# dimmerPower3.net
KiCad netlist of a schematic drawn in EAGLE
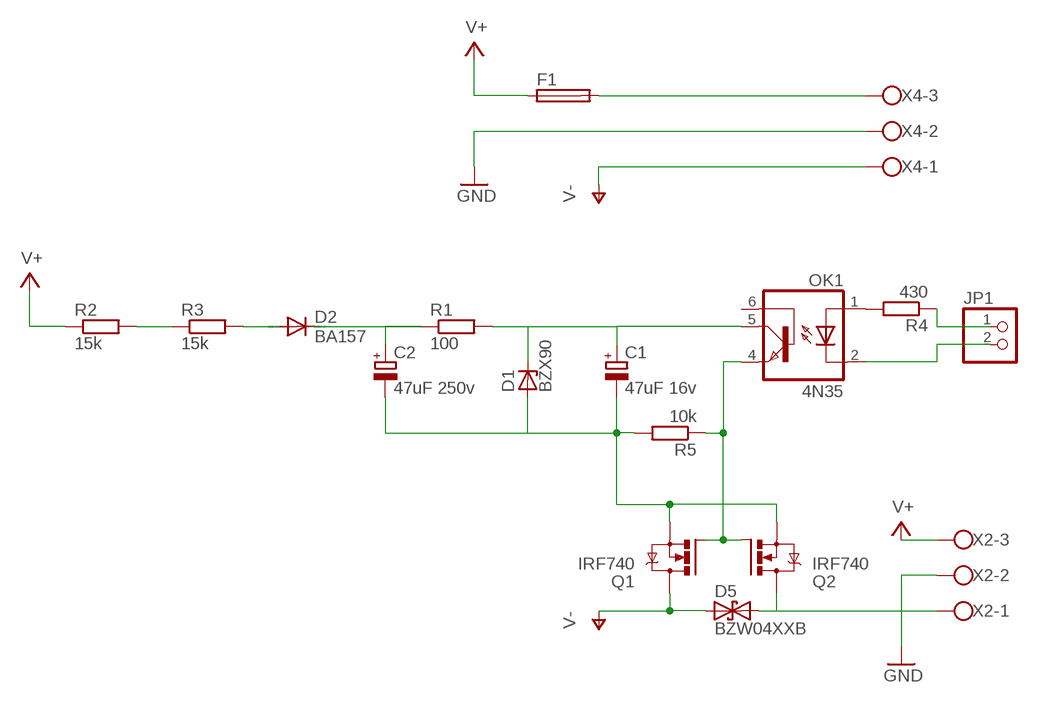
[diagram p0: schematic, sheet 1]

(export (version "E")
  (design (tool "Eeschema 10.0.6"))
  (components
    (comp (ref "C1")
      (value "47uF 16v")
      (footprint "eagle-import:E2,5-6")
      (libsource (lib "eagle-import") (part "CPOL-EUE2.5-6"))
    )
    (comp (ref "C2")
      (value "47uF 250v")
      (footprint "eagle-import:E5-13")
      (libsource (lib "eagle-import") (part "CPOL-EUE5-13"))
    )
    (comp (ref "D1")
      (value "BZX90")
      (footprint "eagle-import:DO34Z7")
      (libsource (lib "eagle-import") (part "BZX90"))
    )
    (comp (ref "D2")
      (value "BA157")
      (footprint "eagle-import:P1-10")
      (libsource (lib "eagle-import") (part "BA157"))
    )
    (comp (ref "D5")
      (value "BZW04XXB")
      (footprint "eagle-import:F126Z12")
      (libsource (lib "eagle-import") (part "BZW04XXB"))
    )
    (comp (ref "F1")
      (value "SH22,5")
      (footprint "eagle-import:SH22,5")
      (fields (field (name "MF") "SCHURTER") (field (name "MPN") "0031.8201"))
      (libsource (lib "eagle-import") (part "SH22,5"))
    )
    (comp (ref "JP1")
      (value "PINHD-1X2")
      (footprint "eagle-import:1X02")
      (libsource (lib "eagle-import") (part "PINHD-1X2"))
    )
    (comp (ref "OK1")
      (value "4N35")
      (footprint "eagle-import:DIL06")
      (fields (field (name "MF") "FAIRCHILD SEMICONDUCTOR"))
      (libsource (lib "eagle-import") (part "4N35"))
    )
    (comp (ref "Q1")
      (value "IRF740")
      (footprint "eagle-import:TO220BV")
      (libsource (lib "eagle-import") (part "IRF740"))
    )
    (comp (ref "Q2")
      (value "IRF740")
      (footprint "eagle-import:TO220BV")
      (libsource (lib "eagle-import") (part "IRF740"))
    )
    (comp (ref "R1")
      (value "100")
      (footprint "eagle-import:0204_7")
      (libsource (lib "eagle-import") (part "R-EU_0204/7"))
    )
    (comp (ref "R2")
      (value "15k")
      (footprint "eagle-import:P0613_15")
      (libsource (lib "eagle-import") (part "R-EU_0613/15"))
    )
    (comp (ref "R3")
      (value "15k")
      (footprint "eagle-import:P0613_15")
      (libsource (lib "eagle-import") (part "R-EU_0613/15"))
    )
    (comp (ref "R4")
      (value "430")
      (footprint "eagle-import:0204_7")
      (libsource (lib "eagle-import") (part "R-EU_0204/7"))
    )
    (comp (ref "R5")
      (value "10k")
      (footprint "eagle-import:0204_7")
      (libsource (lib "eagle-import") (part "R-EU_0204/7"))
    )
    (comp (ref "X2")
      (value "W237-103")
      (footprint "eagle-import:W237-103")
      (fields (field (name "MPN") "237-103"))
      (libsource (lib "eagle-import") (part "W237-103"))
    )
    (comp (ref "X4")
      (value "W237-103")
      (footprint "eagle-import:W237-103")
      (fields (field (name "MPN") "237-103"))
      (libsource (lib "eagle-import") (part "W237-103"))
    )
  )
  (nets
    (net (code "1") (name "GND") (class "Default")
      (node (ref "X2") (pin "2") (pinfunction "KL_2") (pintype "passive"))
      (node (ref "X4") (pin "2") (pinfunction "KL_2") (pintype "passive"))
    )
    (net (code "2") (name "Net-(C1-Pad-)") (class "Default")
      (node (ref "C1") (pin "-") (pinfunction "-_-") (pintype "passive"))
      (node (ref "C2") (pin "-") (pinfunction "-_-") (pintype "passive"))
      (node (ref "D1") (pin "A") (pinfunction "A_A") (pintype "passive"))
      (node (ref "Q1") (pin "S") (pinfunction "S_S") (pintype "passive"))
      (node (ref "Q2") (pin "S") (pinfunction "S_S") (pintype "passive"))
      (node (ref "R5") (pin "2") (pinfunction "2_2") (pintype "passive"))
    )
    (net (code "3") (name "Net-(C2-Pad+)") (class "Default")
      (node (ref "C2") (pin "+") (pinfunction "+_+") (pintype "passive"))
      (node (ref "D2") (pin "C") (pinfunction "C_C") (pintype "passive"))
      (node (ref "R1") (pin "1") (pinfunction "1_1") (pintype "passive"))
    )
    (net (code "4") (name "Net-(D2-PadA)") (class "Default")
      (node (ref "D2") (pin "A") (pinfunction "A_A") (pintype "passive"))
      (node (ref "R3") (pin "2") (pinfunction "2_2") (pintype "passive"))
    )
    (net (code "5") (name "Net-(D5-2)") (class "Default")
      (node (ref "D5") (pin "C") (pinfunction "2_C") (pintype "passive"))
      (node (ref "Q2") (pin "D") (pinfunction "D_D") (pintype "passive"))
      (node (ref "X2") (pin "1") (pinfunction "KL_1") (pintype "passive"))
    )
    (net (code "6") (name "Net-(JP1-Pad1)") (class "Default")
      (node (ref "JP1") (pin "1") (pinfunction "1_1") (pintype "passive"))
      (node (ref "R4") (pin "1") (pinfunction "1_1") (pintype "passive"))
    )
    (net (code "7") (name "Net-(OK1-A)") (class "Default")
      (node (ref "OK1") (pin "1") (pinfunction "A_1") (pintype "passive"))
      (node (ref "R4") (pin "2") (pinfunction "2_2") (pintype "passive"))
    )
    (net (code "8") (name "Net-(OK1-C)") (class "Default")
      (node (ref "JP1") (pin "2") (pinfunction "2_2") (pintype "passive"))
      (node (ref "OK1") (pin "2") (pinfunction "C_2") (pintype "passive"))
    )
    (net (code "9") (name "Net-(OK1-COL)") (class "Default")
      (node (ref "C1") (pin "+") (pinfunction "+_+") (pintype "passive"))
      (node (ref "D1") (pin "C") (pinfunction "C_C") (pintype "passive"))
      (node (ref "OK1") (pin "5") (pinfunction "COL_5") (pintype "passive"))
      (node (ref "R1") (pin "2") (pinfunction "2_2") (pintype "passive"))
    )
    (net (code "10") (name "Net-(OK1-EMI)") (class "Default")
      (node (ref "OK1") (pin "4") (pinfunction "EMI_4") (pintype "passive"))
      (node (ref "Q1") (pin "G") (pinfunction "G_G") (pintype "passive"))
      (node (ref "Q2") (pin "G") (pinfunction "G_G") (pintype "passive"))
      (node (ref "R5") (pin "1") (pinfunction "1_1") (pintype "passive"))
    )
    (net (code "11") (name "Net-(R2-Pad2)") (class "Default")
      (node (ref "R2") (pin "2") (pinfunction "2_2") (pintype "passive"))
      (node (ref "R3") (pin "1") (pinfunction "1_1") (pintype "passive"))
    )
    (net (code "12") (name "Net-(X4C-KL)") (class "Default")
      (node (ref "F1") (pin "2") (pinfunction "2_2") (pintype "passive"))
      (node (ref "X4") (pin "3") (pinfunction "KL_3") (pintype "passive"))
    )
    (net (code "13") (name "V+") (class "Default")
      (node (ref "F1") (pin "1") (pinfunction "1_1") (pintype "passive"))
      (node (ref "R2") (pin "1") (pinfunction "1_1") (pintype "passive"))
      (node (ref "X2") (pin "3") (pinfunction "KL_3") (pintype "passive"))
    )
    (net (code "14") (name "V-") (class "Default")
      (node (ref "D5") (pin "A") (pinfunction "1_A") (pintype "passive"))
      (node (ref "Q1") (pin "D") (pinfunction "D_D") (pintype "passive"))
      (node (ref "X4") (pin "1") (pinfunction "KL_1") (pintype "passive"))
    )
    (net (code "15") (name "unconnected-(OK1-BAS-Pad6)") (class "Default")
      (node (ref "OK1") (pin "6") (pinfunction "BAS_6") (pintype "passive"))
    )
  )
)
